# pic.net
KiCad netlist of a schematic drawn in Altium Designer
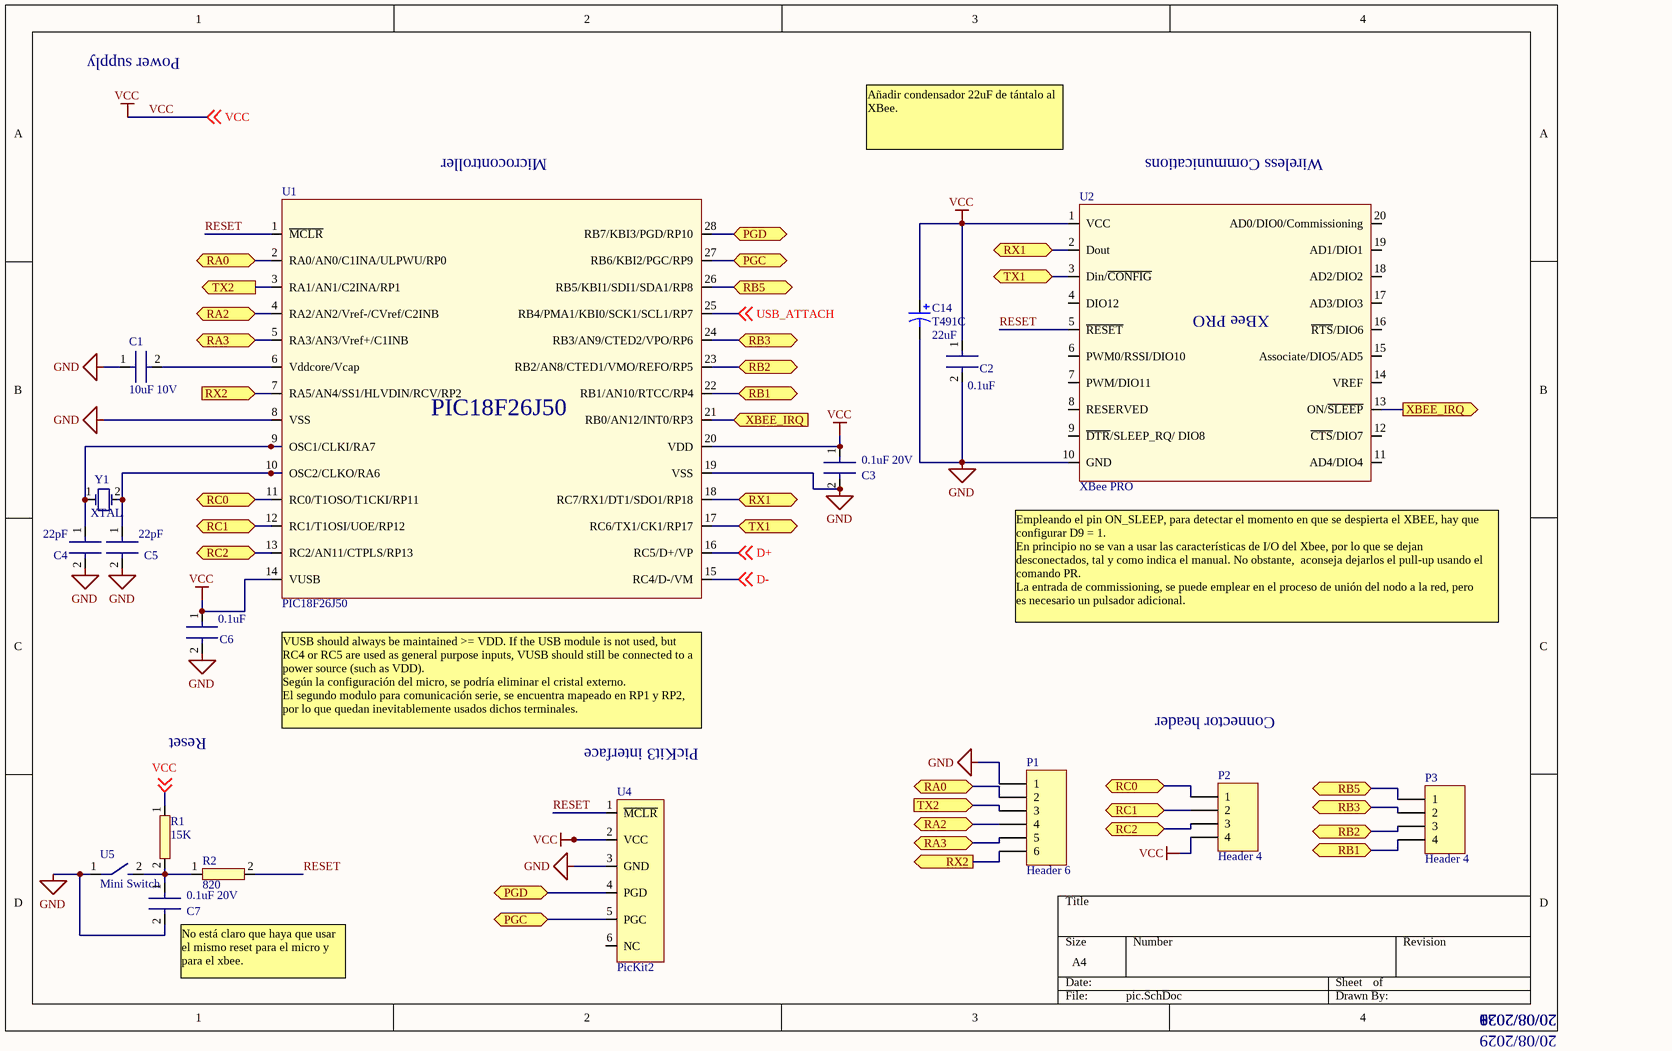
[diagram p0: pic.SchDoc]

(export (version "E")
  (design (tool "Eeschema 10.0.6"))
  (components
    (comp (ref "C1")
      (value "10uF 10V")
      (footprint "C1206")
      (libsource (lib "uMote") (part "TDK C3216X7R1C106K"))
    )
    (comp (ref "C2")
      (value "0.1uF")
      (footprint "C1206")
      (libsource (lib "uMote") (part "TDK C3216X7R1C106K"))
    )
    (comp (ref "C3")
      (value "0.1uF 20V")
      (footprint "C1206")
      (libsource (lib "uMote") (part "TDK C3216X7R1C106K"))
    )
    (comp (ref "C4") (value "22pF") (footprint "C0805") (libsource (lib "uMote") (part "TDK C3216X7R1C106K")))
    (comp (ref "C5") (value "22pF") (footprint "C0805") (libsource (lib "uMote") (part "TDK C3216X7R1C106K")))
    (comp (ref "C6")
      (value "0.1uF")
      (footprint "C1206")
      (libsource (lib "uMote") (part "TDK C3216X7R1C106K"))
    )
    (comp (ref "C7")
      (value "0.1uF 20V")
      (footprint "C1206")
      (libsource (lib "uMote") (part "TDK C3216X7R1C106K"))
    )
    (comp (ref "C14")
      (value "T491C")
      (footprint "C")
      (description "Solid Tantalum Chip Capacitor, Standard T491 Series - Industrial Grade")
      (fields (field (name "ALTIUM_VALUE") "22uF") (field (name "PUBLISHER") "Altium Limited"))
      (libsource (lib "KEMET Chip Capacitor") (part "T491C"))
    )
    (comp (ref "P1")
      (value "Header 6")
      (footprint "HDR1X6")
      (description "Header, 6-Pin")
      (fields (field (name "PUBLISHER") "Altium Limited"))
      (libsource (lib "Miscellaneous Connectors") (part "Header 6"))
    )
    (comp (ref "P2")
      (value "Header 4")
      (footprint "HDR1X4")
      (description "Header, 4-Pin")
      (fields (field (name "PUBLISHER") "Altium Limited"))
      (libsource (lib "Miscellaneous Connectors") (part "Header 4"))
    )
    (comp (ref "P3")
      (value "Header 4")
      (footprint "HDR1X4")
      (description "Header, 4-Pin")
      (fields (field (name "PUBLISHER") "Altium Limited"))
      (libsource (lib "Miscellaneous Connectors") (part "Header 4"))
    )
    (comp (ref "R1") (value "15K") (footprint "3216[1206]") (libsource (lib "uMote") (part "RES 1206")))
    (comp (ref "R2") (value "820") (footprint "3216[1206]") (libsource (lib "") (part "RES 1206_1")))
    (comp (ref "U1")
      (value "PIC18F26J50")
      (footprint "PIC18F-SOIC")
      (libsource (lib "uMote") (part "PIC18F26J50"))
    )
    (comp (ref "U2") (value "XBee PRO") (footprint "XBee PRO") (libsource (lib "uMote") (part "XBee PRO")))
    (comp (ref "U4") (value "PicKit2") (footprint "PICKIT3") (libsource (lib "uMote") (part "PicKit2")))
    (comp (ref "U5")
      (value "Mini Switch")
      (footprint "Mini Switch")
      (libsource (lib "uMote") (part "Mini Switch"))
    )
    (comp (ref "Y1") (value "XTAL") (footprint "HC-49/US") (libsource (lib "uMote") (part "XTAL")))
  )
  (nets
    (net (code "1") (name "/PGC") (class "Default")
      (node (ref "U1") (pin "27") (pinfunction "RB6/KBI2/PGC/RP9_27") (pintype "passive"))
      (node (ref "U4") (pin "5") (pinfunction "PGC_5") (pintype "passive"))
    )
    (net (code "2") (name "/PGD") (class "Default")
      (node (ref "U1") (pin "28") (pinfunction "RB7/KBI3/PGD/RP10_28") (pintype "passive"))
      (node (ref "U4") (pin "4") (pinfunction "PGD_4") (pintype "passive"))
    )
    (net (code "3") (name "/RA0") (class "Default")
      (node (ref "P1") (pin "2") (pinfunction "2_2") (pintype "passive"))
      (node (ref "U1") (pin "2") (pinfunction "RA0/AN0/C1INA/ULPWU/RP0_2") (pintype "passive"))
    )
    (net (code "4") (name "/RA2") (class "Default")
      (node (ref "P1") (pin "4") (pinfunction "4_4") (pintype "passive"))
      (node (ref "U1") (pin "4") (pinfunction "RA2/AN2/Vref-/CVref/C2INB_4") (pintype "passive"))
    )
    (net (code "5") (name "/RA3") (class "Default")
      (node (ref "P1") (pin "5") (pinfunction "5_5") (pintype "passive"))
      (node (ref "U1") (pin "5") (pinfunction "RA3/AN3/Vref+/C1INB_5") (pintype "passive"))
    )
    (net (code "6") (name "/RB1") (class "Default")
      (node (ref "P3") (pin "4") (pinfunction "4_4") (pintype "passive"))
      (node (ref "U1") (pin "22") (pinfunction "RB1/AN10/RTCC/RP4_22") (pintype "passive"))
    )
    (net (code "7") (name "/RB2") (class "Default")
      (node (ref "P3") (pin "3") (pinfunction "3_3") (pintype "passive"))
      (node (ref "U1") (pin "23") (pinfunction "RB2/AN8/CTED1/VMO/REFO/RP5_23") (pintype "passive"))
    )
    (net (code "8") (name "/RB3") (class "Default")
      (node (ref "P3") (pin "2") (pinfunction "2_2") (pintype "passive"))
      (node (ref "U1") (pin "24") (pinfunction "RB3/AN9/CTED2/VPO/RP6_24") (pintype "passive"))
    )
    (net (code "9") (name "/RB5") (class "Default")
      (node (ref "P3") (pin "1") (pinfunction "1_1") (pintype "passive"))
      (node (ref "U1") (pin "26") (pinfunction "RB5/KBI1/SDI1/SDA1/RP8_26") (pintype "passive"))
    )
    (net (code "10") (name "/RC0") (class "Default")
      (node (ref "P2") (pin "1") (pinfunction "1_1") (pintype "passive"))
      (node (ref "U1") (pin "11") (pinfunction "RC0/T1OSO/T1CKI/RP11_11") (pintype "passive"))
    )
    (net (code "11") (name "/RC1") (class "Default")
      (node (ref "P2") (pin "2") (pinfunction "2_2") (pintype "passive"))
      (node (ref "U1") (pin "12") (pinfunction "RC1/T1OSI/UOE/RP12_12") (pintype "passive"))
    )
    (net (code "12") (name "/RC2") (class "Default")
      (node (ref "P2") (pin "3") (pinfunction "3_3") (pintype "passive"))
      (node (ref "U1") (pin "13") (pinfunction "RC2/AN11/CTPLS/RP13_13") (pintype "passive"))
    )
    (net (code "13") (name "/RESET") (class "Default")
      (node (ref "R2") (pin "2") (pinfunction "2_2") (pintype "passive"))
      (node (ref "U1") (pin "1") (pinfunction "MCLR_1") (pintype "input"))
      (node (ref "U2") (pin "5") (pinfunction "RESET_5") (pintype "passive"))
      (node (ref "U4") (pin "1") (pinfunction "MCLR_1") (pintype "passive"))
    )
    (net (code "14") (name "/RX1") (class "Default")
      (node (ref "U1") (pin "18") (pinfunction "RC7/RX1/DT1/SDO1/RP18_18") (pintype "passive"))
      (node (ref "U2") (pin "2") (pinfunction "Dout_2") (pintype "passive"))
    )
    (net (code "15") (name "/RX2") (class "Default")
      (node (ref "P1") (pin "6") (pinfunction "6_6") (pintype "passive"))
      (node (ref "U1") (pin "7") (pinfunction "RA5/AN4/SS1/HLVDIN/RCV/RP2_7") (pintype "passive"))
    )
    (net (code "16") (name "/TX1") (class "Default")
      (node (ref "U1") (pin "17") (pinfunction "RC6/TX1/CK1/RP17_17") (pintype "passive"))
      (node (ref "U2") (pin "3") (pinfunction "Din/~{CONFIG}_3") (pintype "passive"))
    )
    (net (code "17") (name "/TX2") (class "Default")
      (node (ref "P1") (pin "3") (pinfunction "3_3") (pintype "passive"))
      (node (ref "U1") (pin "3") (pinfunction "RA1/AN1/C2INA/RP1_3") (pintype "passive"))
    )
    (net (code "18") (name "/XBEE_IRQ") (class "Default")
      (node (ref "U1") (pin "21") (pinfunction "RB0/AN12/INT0/RP3_21") (pintype "passive"))
      (node (ref "U2") (pin "13") (pinfunction "ON/~{SLEEP}_13") (pintype "passive"))
    )
    (net (code "19") (name "D+") (class "Default")
      (node (ref "U1") (pin "16") (pinfunction "RC5/D+/VP_16") (pintype "passive"))
    )
    (net (code "20") (name "D-") (class "Default")
      (node (ref "U1") (pin "15") (pinfunction "RC4/D-/VM_15") (pintype "passive"))
    )
    (net (code "21") (name "GND") (class "Default")
      (node (ref "C1") (pin "1") (pinfunction "1_1") (pintype "passive"))
      (node (ref "C14") (pin "2") (pinfunction "2_2") (pintype "passive"))
      (node (ref "C2") (pin "2") (pinfunction "2_2") (pintype "passive"))
      (node (ref "C3") (pin "2") (pinfunction "2_2") (pintype "passive"))
      (node (ref "C4") (pin "2") (pinfunction "2_2") (pintype "passive"))
      (node (ref "C5") (pin "2") (pinfunction "2_2") (pintype "passive"))
      (node (ref "C6") (pin "2") (pinfunction "2_2") (pintype "passive"))
      (node (ref "C7") (pin "2") (pinfunction "2_2") (pintype "passive"))
      (node (ref "P1") (pin "1") (pinfunction "1_1") (pintype "passive"))
      (node (ref "U1") (pin "19") (pinfunction "VSS_19") (pintype "passive"))
      (node (ref "U1") (pin "8") (pinfunction "VSS_8") (pintype "passive"))
      (node (ref "U2") (pin "10") (pinfunction "GND_10") (pintype "passive"))
      (node (ref "U4") (pin "3") (pinfunction "GND_3") (pintype "passive"))
      (node (ref "U5") (pin "1") (pinfunction "1_1") (pintype "passive"))
    )
    (net (code "22") (name "Net-(C7-Pad1)") (class "Default")
      (node (ref "C7") (pin "1") (pinfunction "1_1") (pintype "passive"))
      (node (ref "R1") (pin "2") (pinfunction "2_2") (pintype "passive"))
      (node (ref "R2") (pin "1") (pinfunction "1_1") (pintype "passive"))
      (node (ref "U5") (pin "2") (pinfunction "2_2") (pintype "passive"))
    )
    (net (code "23") (name "Net-(U1-OSC1{slash}CLKI{slash}RA7)") (class "Default")
      (node (ref "C4") (pin "1") (pinfunction "1_1") (pintype "passive"))
      (node (ref "U1") (pin "9") (pinfunction "OSC1/CLKI/RA7_9") (pintype "passive"))
      (node (ref "Y1") (pin "1") (pinfunction "+_1") (pintype "passive"))
    )
    (net (code "24") (name "Net-(U1-OSC2{slash}CLKO{slash}RA6)") (class "Default")
      (node (ref "C5") (pin "1") (pinfunction "1_1") (pintype "passive"))
      (node (ref "U1") (pin "10") (pinfunction "OSC2/CLKO/RA6_10") (pintype "passive"))
      (node (ref "Y1") (pin "2") (pinfunction "-_2") (pintype "passive"))
    )
    (net (code "25") (name "Net-(U1-Vddcore{slash}Vcap)") (class "Default")
      (node (ref "C1") (pin "2") (pinfunction "2_2") (pintype "passive"))
      (node (ref "U1") (pin "6") (pinfunction "Vddcore/Vcap_6") (pintype "passive"))
    )
    (net (code "26") (name "USB_ATTACH") (class "Default")
      (node (ref "U1") (pin "25") (pinfunction "RB4/PMA1/KBI0/SCK1/SCL1/RP7_25") (pintype "passive"))
    )
    (net (code "27") (name "VCC") (class "Default")
      (node (ref "C14") (pin "1") (pinfunction "1_1") (pintype "passive"))
      (node (ref "C2") (pin "1") (pinfunction "1_1") (pintype "passive"))
      (node (ref "C3") (pin "1") (pinfunction "1_1") (pintype "passive"))
      (node (ref "C6") (pin "1") (pinfunction "1_1") (pintype "passive"))
      (node (ref "P2") (pin "4") (pinfunction "4_4") (pintype "passive"))
      (node (ref "R1") (pin "1") (pinfunction "1_1") (pintype "passive"))
      (node (ref "U1") (pin "14") (pinfunction "VUSB_14") (pintype "passive"))
      (node (ref "U1") (pin "20") (pinfunction "VDD_20") (pintype "passive"))
      (node (ref "U2") (pin "1") (pinfunction "VCC_1") (pintype "passive"))
      (node (ref "U4") (pin "2") (pinfunction "VCC_2") (pintype "passive"))
    )
    (net (code "28") (name "unconnected-(U2-AD0{slash}DIO0{slash}Commissioning-Pad20)") (class "Default")
      (node (ref "U2") (pin "20") (pinfunction "AD0/DIO0/Commissioning_20") (pintype "passive"))
    )
    (net (code "29") (name "unconnected-(U2-AD1{slash}DIO1-Pad19)") (class "Default")
      (node (ref "U2") (pin "19") (pinfunction "AD1/DIO1_19") (pintype "passive"))
    )
    (net (code "30") (name "unconnected-(U2-AD2{slash}DIO2-Pad18)") (class "Default")
      (node (ref "U2") (pin "18") (pinfunction "AD2/DIO2_18") (pintype "passive"))
    )
    (net (code "31") (name "unconnected-(U2-AD3{slash}DIO3-Pad17)") (class "Default")
      (node (ref "U2") (pin "17") (pinfunction "AD3/DIO3_17") (pintype "passive"))
    )
    (net (code "32") (name "unconnected-(U2-AD4{slash}DIO4-Pad11)") (class "Default")
      (node (ref "U2") (pin "11") (pinfunction "AD4/DIO4_11") (pintype "passive"))
    )
    (net (code "33") (name "unconnected-(U2-Associate{slash}DIO5{slash}AD5-Pad15)") (class "Default")
      (node (ref "U2") (pin "15") (pinfunction "Associate/DIO5/AD5_15") (pintype "passive"))
    )
    (net (code "34") (name "unconnected-(U2-DIO12-Pad4)") (class "Default")
      (node (ref "U2") (pin "4") (pinfunction "DIO12_4") (pintype "passive"))
    )
    (net (code "35") (name "unconnected-(U2-PWM0{slash}RSSI{slash}DIO10-Pad6)") (class "Default")
      (node (ref "U2") (pin "6") (pinfunction "PWM0/RSSI/DIO10_6") (pintype "passive"))
    )
    (net (code "36") (name "unconnected-(U2-PWM{slash}DIO11-Pad7)") (class "Default")
      (node (ref "U2") (pin "7") (pinfunction "PWM/DIO11_7") (pintype "passive"))
    )
    (net (code "37") (name "unconnected-(U2-RESERVED-Pad8)") (class "Default")
      (node (ref "U2") (pin "8") (pinfunction "RESERVED_8") (pintype "passive"))
    )
    (net (code "38") (name "unconnected-(U2-VREF-Pad14)") (class "Default")
      (node (ref "U2") (pin "14") (pinfunction "VREF_14") (pintype "passive"))
    )
    (net (code "39") (name "unconnected-(U2-~{CTS}{slash}DIO7-Pad12)") (class "Default")
      (node (ref "U2") (pin "12") (pinfunction "~{CTS}/DIO7_12") (pintype "passive"))
    )
    (net (code "40") (name "unconnected-(U2-~{DTR}{slash}SLEEP_RQ{slash}_DIO8-Pad9)") (class "Default")
      (node (ref "U2") (pin "9") (pinfunction "~{DTR}/SLEEP_RQ/_DIO8_9") (pintype "passive"))
    )
    (net (code "41") (name "unconnected-(U2-~{RTS}{slash}DIO6-Pad16)") (class "Default")
      (node (ref "U2") (pin "16") (pinfunction "~{RTS}/DIO6_16") (pintype "passive"))
    )
    (net (code "42") (name "unconnected-(U4-NC-Pad6)") (class "Default")
      (node (ref "U4") (pin "6") (pinfunction "NC_6") (pintype "passive"))
    )
  )
)
